# bilancia_smart_full.net
KiCad netlist of a schematic drawn in EAGLE
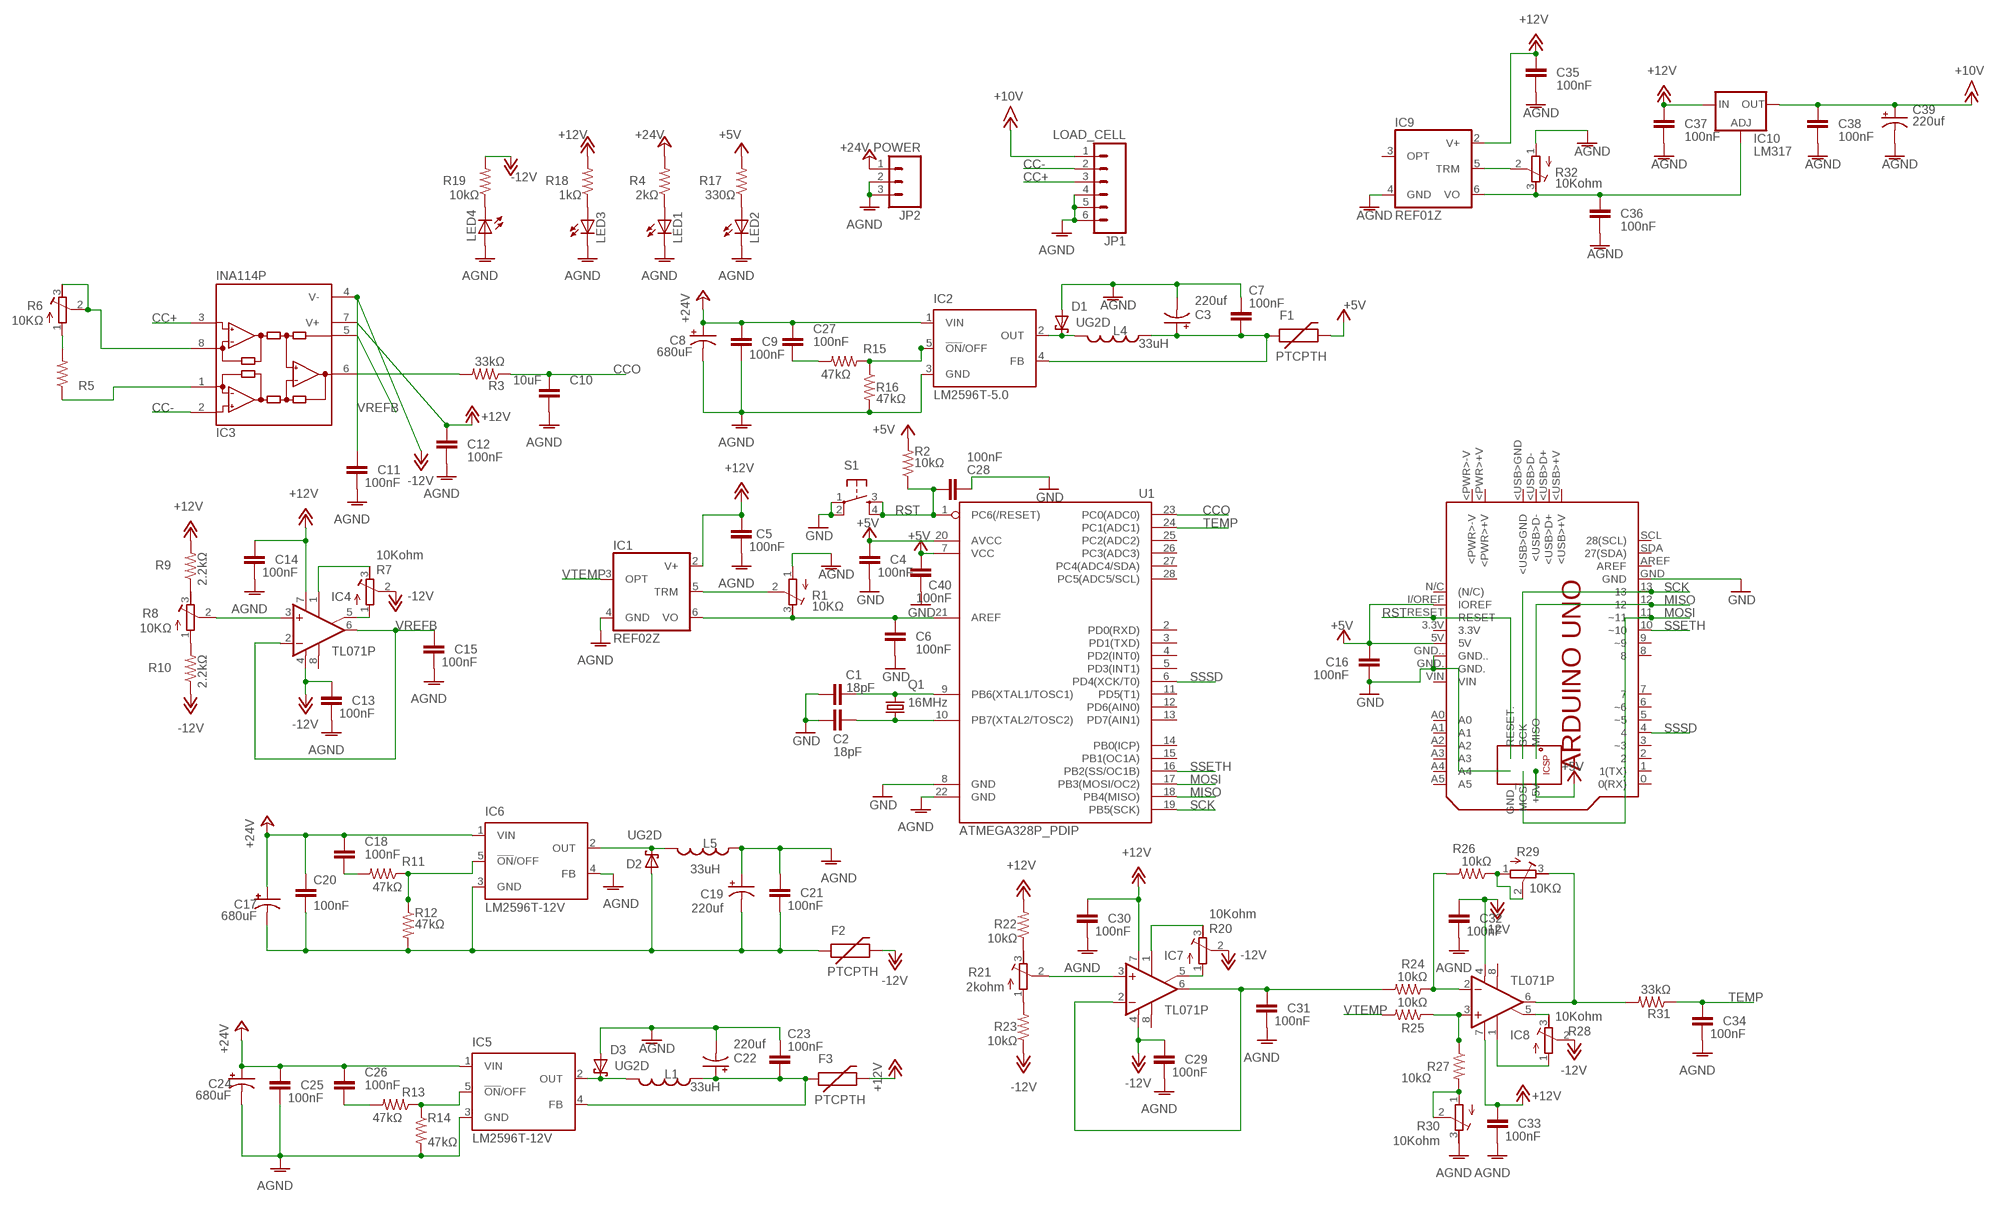
[diagram p0: schematic, sheet 1]

(export (version "E")
  (design (tool "Eeschema 10.0.6"))
  (components
    (comp (ref "C1")
      (value "18pF")
      (footprint "eagle-import:C2.5-2")
      (libsource (lib "eagle-import") (part "C2.5/2"))
    )
    (comp (ref "C2")
      (value "18pF")
      (footprint "eagle-import:C2.5-2")
      (libsource (lib "eagle-import") (part "C2.5/2"))
    )
    (comp (ref "C3")
      (value "220uf")
      (footprint "eagle-import:E5-8,5")
      (libsource (lib "eagle-import") (part "CPOL-USE5-8.5"))
    )
    (comp (ref "C4")
      (value "100nF")
      (footprint "eagle-import:C2.5-2")
      (libsource (lib "eagle-import") (part "C2.5/2"))
    )
    (comp (ref "C5")
      (value "100nF")
      (footprint "eagle-import:C2.5-2")
      (libsource (lib "eagle-import") (part "C2.5/2"))
    )
    (comp (ref "C6")
      (value "100nF")
      (footprint "eagle-import:C2.5-2")
      (libsource (lib "eagle-import") (part "C2.5/2"))
    )
    (comp (ref "C7")
      (value "100nF")
      (footprint "eagle-import:C2.5-2")
      (libsource (lib "eagle-import") (part "C2.5/2"))
    )
    (comp (ref "C8")
      (value "680uF")
      (footprint "eagle-import:E5-8,5")
      (libsource (lib "eagle-import") (part "CPOL-USE5-8.5"))
    )
    (comp (ref "C9")
      (value "100nF")
      (footprint "eagle-import:C2.5-2")
      (libsource (lib "eagle-import") (part "C2.5/2"))
    )
    (comp (ref "C10")
      (value "10uF")
      (footprint "eagle-import:C2.5-2")
      (libsource (lib "eagle-import") (part "C2.5/2"))
    )
    (comp (ref "C11")
      (value "100nF")
      (footprint "eagle-import:C2.5-2")
      (libsource (lib "eagle-import") (part "C2.5/2"))
    )
    (comp (ref "C12")
      (value "100nF")
      (footprint "eagle-import:C2.5-2")
      (libsource (lib "eagle-import") (part "C2.5/2"))
    )
    (comp (ref "C13")
      (value "100nF")
      (footprint "eagle-import:C2.5-2")
      (libsource (lib "eagle-import") (part "C2.5/2"))
    )
    (comp (ref "C14")
      (value "100nF")
      (footprint "eagle-import:C2.5-2")
      (libsource (lib "eagle-import") (part "C2.5/2"))
    )
    (comp (ref "C15")
      (value "100nF")
      (footprint "eagle-import:C2.5-2")
      (libsource (lib "eagle-import") (part "C2.5/2"))
    )
    (comp (ref "C16")
      (value "100nF")
      (footprint "eagle-import:C2.5-2")
      (libsource (lib "eagle-import") (part "C2.5/2"))
    )
    (comp (ref "C17")
      (value "680uF")
      (footprint "eagle-import:E5-8,5")
      (libsource (lib "eagle-import") (part "CPOL-USE5-8.5"))
    )
    (comp (ref "C18")
      (value "100nF")
      (footprint "eagle-import:C2.5-2")
      (libsource (lib "eagle-import") (part "C2.5/2"))
    )
    (comp (ref "C19")
      (value "220uf")
      (footprint "eagle-import:E5-8,5")
      (libsource (lib "eagle-import") (part "CPOL-USE5-8.5"))
    )
    (comp (ref "C20")
      (value "100nF")
      (footprint "eagle-import:C2.5-2")
      (libsource (lib "eagle-import") (part "C2.5/2"))
    )
    (comp (ref "C21")
      (value "100nF")
      (footprint "eagle-import:C2.5-2")
      (libsource (lib "eagle-import") (part "C2.5/2"))
    )
    (comp (ref "C22")
      (value "220uf")
      (footprint "eagle-import:E5-8,5")
      (libsource (lib "eagle-import") (part "CPOL-USE5-8.5"))
    )
    (comp (ref "C23")
      (value "100nF")
      (footprint "eagle-import:C2.5-2")
      (libsource (lib "eagle-import") (part "C2.5/2"))
    )
    (comp (ref "C24")
      (value "680uF")
      (footprint "eagle-import:E5-8,5")
      (libsource (lib "eagle-import") (part "CPOL-USE5-8.5"))
    )
    (comp (ref "C25")
      (value "100nF")
      (footprint "eagle-import:C2.5-2")
      (libsource (lib "eagle-import") (part "C2.5/2"))
    )
    (comp (ref "C26")
      (value "100nF")
      (footprint "eagle-import:C2.5-2")
      (libsource (lib "eagle-import") (part "C2.5/2"))
    )
    (comp (ref "C27")
      (value "100nF")
      (footprint "eagle-import:C2.5-2")
      (libsource (lib "eagle-import") (part "C2.5/2"))
    )
    (comp (ref "C28")
      (value "100nF")
      (footprint "eagle-import:C2.5-2")
      (libsource (lib "eagle-import") (part "C2.5/2"))
    )
    (comp (ref "C29")
      (value "100nF")
      (footprint "eagle-import:C2.5-2")
      (libsource (lib "eagle-import") (part "C2.5/2"))
    )
    (comp (ref "C30")
      (value "100nF")
      (footprint "eagle-import:C2.5-2")
      (libsource (lib "eagle-import") (part "C2.5/2"))
    )
    (comp (ref "C31")
      (value "100nF")
      (footprint "eagle-import:C2.5-2")
      (libsource (lib "eagle-import") (part "C2.5/2"))
    )
    (comp (ref "C32")
      (value "100nF")
      (footprint "eagle-import:C2.5-2")
      (libsource (lib "eagle-import") (part "C2.5/2"))
    )
    (comp (ref "C33")
      (value "100nF")
      (footprint "eagle-import:C2.5-2")
      (libsource (lib "eagle-import") (part "C2.5/2"))
    )
    (comp (ref "C34")
      (value "100nF")
      (footprint "eagle-import:C2.5-2")
      (libsource (lib "eagle-import") (part "C2.5/2"))
    )
    (comp (ref "C35")
      (value "100nF")
      (footprint "eagle-import:C2.5-2")
      (libsource (lib "eagle-import") (part "C2.5/2"))
    )
    (comp (ref "C36")
      (value "100nF")
      (footprint "eagle-import:C2.5-2")
      (libsource (lib "eagle-import") (part "C2.5/2"))
    )
    (comp (ref "C37")
      (value "100nF")
      (footprint "eagle-import:C2.5-2")
      (libsource (lib "eagle-import") (part "C2.5/2"))
    )
    (comp (ref "C38")
      (value "100nF")
      (footprint "eagle-import:C2.5-2")
      (libsource (lib "eagle-import") (part "C2.5/2"))
    )
    (comp (ref "C39")
      (value "220uf")
      (footprint "eagle-import:E5-8,5")
      (libsource (lib "eagle-import") (part "CPOL-USE5-8.5"))
    )
    (comp (ref "C40")
      (value "100nF")
      (footprint "eagle-import:C2.5-2")
      (libsource (lib "eagle-import") (part "C2.5/2"))
    )
    (comp (ref "D1")
      (value "UG2D")
      (footprint "eagle-import:DO41-7")
      (libsource (lib "eagle-import") (part "SCHOTTKY-DIODEDO41-7"))
    )
    (comp (ref "D2")
      (value "UG2D")
      (footprint "eagle-import:DO41-7")
      (libsource (lib "eagle-import") (part "SCHOTTKY-DIODEDO41-7"))
    )
    (comp (ref "D3")
      (value "UG2D")
      (footprint "eagle-import:DO41-7")
      (libsource (lib "eagle-import") (part "SCHOTTKY-DIODEDO41-7"))
    )
    (comp (ref "F1")
      (value "PTCPTH")
      (footprint "eagle-import:PTC")
      (libsource (lib "eagle-import") (part "PTCPTH"))
    )
    (comp (ref "F2")
      (value "PTCPTH")
      (footprint "eagle-import:PTC")
      (libsource (lib "eagle-import") (part "PTCPTH"))
    )
    (comp (ref "F3")
      (value "PTCPTH")
      (footprint "eagle-import:PTC")
      (libsource (lib "eagle-import") (part "PTCPTH"))
    )
    (comp (ref "IC1")
      (value "REF02Z")
      (footprint "eagle-import:DIL08")
      (libsource (lib "eagle-import") (part "REF02Z"))
    )
    (comp (ref "IC2")
      (value "LM2596T-5.0")
      (footprint "eagle-import:T05D")
      (fields (field (name "MPN") "LM2596T-ADJ/LF02"))
      (libsource (lib "eagle-import") (part "LM2596T"))
    )
    (comp (ref "IC3")
      (value "INA114P")
      (footprint "eagle-import:DIL08")
      (fields (field (name "MF") "TEXAS INSTRUMENTS") (field (name "MPN") "INA114BP"))
      (libsource (lib "eagle-import") (part "INA114P"))
    )
    (comp (ref "IC4")
      (value "TL071P")
      (footprint "eagle-import:DIL08")
      (libsource (lib "eagle-import") (part "TL071P"))
    )
    (comp (ref "IC5")
      (value "LM2596T-12V")
      (footprint "eagle-import:T05D")
      (fields (field (name "MPN") "LM2596T-ADJ/LF02"))
      (libsource (lib "eagle-import") (part "LM2596T"))
    )
    (comp (ref "IC6")
      (value "LM2596T-12V")
      (footprint "eagle-import:T05D")
      (fields (field (name "MPN") "LM2596T-ADJ/LF02"))
      (libsource (lib "eagle-import") (part "LM2596T"))
    )
    (comp (ref "IC7")
      (value "TL071P")
      (footprint "eagle-import:DIL08")
      (libsource (lib "eagle-import") (part "TL071P"))
    )
    (comp (ref "IC8")
      (value "TL071P")
      (footprint "eagle-import:DIL08")
      (libsource (lib "eagle-import") (part "TL071P"))
    )
    (comp (ref "IC9")
      (value "REF01Z")
      (footprint "eagle-import:DIL08")
      (libsource (lib "eagle-import") (part "REF01Z"))
    )
    (comp (ref "IC10")
      (value "LM317")
      (footprint "eagle-import:317TL")
      (libsource (lib "eagle-import") (part "LM317TL"))
    )
    (comp (ref "JP1")
      (value "LOAD_CELL")
      (footprint "eagle-import:1X06")
      (libsource (lib "eagle-import") (part "M06SIP"))
    )
    (comp (ref "JP2")
      (value "POWER")
      (footprint "eagle-import:1X03")
      (libsource (lib "eagle-import") (part "M03PTH"))
    )
    (comp (ref "L1")
      (value "33uH")
      (footprint "eagle-import:RLB0912")
      (libsource (lib "eagle-import") (part "INDUCTORRLB0912"))
    )
    (comp (ref "L4")
      (value "33uH")
      (footprint "eagle-import:RLB0912")
      (libsource (lib "eagle-import") (part "INDUCTORRLB0912"))
    )
    (comp (ref "L5")
      (value "33uH")
      (footprint "eagle-import:RLB0912")
      (libsource (lib "eagle-import") (part "INDUCTORRLB0912"))
    )
    (comp (ref "LED1")
      (value "MINIMIDI_LED5MM")
      (footprint "eagle-import:MINIMIDI_LED5MM")
      (libsource (lib "eagle-import") (part "MINIMIDI_LED5MM"))
    )
    (comp (ref "LED2")
      (value "MINIMIDI_LED5MM")
      (footprint "eagle-import:MINIMIDI_LED5MM")
      (libsource (lib "eagle-import") (part "MINIMIDI_LED5MM"))
    )
    (comp (ref "LED3")
      (value "MINIMIDI_LED5MM")
      (footprint "eagle-import:MINIMIDI_LED5MM")
      (libsource (lib "eagle-import") (part "MINIMIDI_LED5MM"))
    )
    (comp (ref "LED4")
      (value "MINIMIDI_LED5MM")
      (footprint "eagle-import:MINIMIDI_LED5MM")
      (libsource (lib "eagle-import") (part "MINIMIDI_LED5MM"))
    )
    (comp (ref "PCB1")
      (value "ARDUINO_UNO")
      (footprint "eagle-import:ARDUINO_UNO")
      (libsource (lib "eagle-import") (part "ARDUINO_UNO"))
    )
    (comp (ref "Q1")
      (value "16MHz")
      (footprint "eagle-import:HC49_S")
      (libsource (lib "eagle-import") (part "CRYSTALHC49S"))
    )
    (comp (ref "R1")
      (value "10KΩ")
      (footprint "eagle-import:RTRIM64W")
      (libsource (lib "eagle-import") (part "R-TRIMM64W"))
    )
    (comp (ref "R2")
      (value "10kΩ")
      (footprint "eagle-import:0207_10")
      (libsource (lib "eagle-import") (part "R-US_0207/10"))
    )
    (comp (ref "R3")
      (value "33kΩ")
      (footprint "eagle-import:0207_10")
      (libsource (lib "eagle-import") (part "R-US_0207/10"))
    )
    (comp (ref "R4")
      (value "2kΩ")
      (footprint "eagle-import:0207_10")
      (libsource (lib "eagle-import") (part "R-US_0207/10"))
    )
    (comp (ref "R5")
      (value "R-US_0207/10")
      (footprint "eagle-import:0207_10")
      (libsource (lib "eagle-import") (part "R-US_0207/10"))
    )
    (comp (ref "R6")
      (value "10KΩ")
      (footprint "eagle-import:RTRIM64W")
      (libsource (lib "eagle-import") (part "R-TRIMM64W"))
    )
    (comp (ref "R7")
      (value "10Kohm")
      (footprint "eagle-import:RTRIM64W")
      (libsource (lib "eagle-import") (part "R-TRIMM64W"))
    )
    (comp (ref "R8")
      (value "10KΩ")
      (footprint "eagle-import:RTRIM64W")
      (libsource (lib "eagle-import") (part "R-TRIMM64W"))
    )
    (comp (ref "R9")
      (value "2.2kΩ")
      (footprint "eagle-import:0207_10")
      (libsource (lib "eagle-import") (part "R-US_0207/10"))
    )
    (comp (ref "R10")
      (value "2.2kΩ")
      (footprint "eagle-import:0207_10")
      (libsource (lib "eagle-import") (part "R-US_0207/10"))
    )
    (comp (ref "R11")
      (value "47kΩ")
      (footprint "eagle-import:0207_10")
      (libsource (lib "eagle-import") (part "R-US_0207/10"))
    )
    (comp (ref "R12")
      (value "47kΩ")
      (footprint "eagle-import:0207_10")
      (libsource (lib "eagle-import") (part "R-US_0207/10"))
    )
    (comp (ref "R13")
      (value "47kΩ")
      (footprint "eagle-import:0207_10")
      (libsource (lib "eagle-import") (part "R-US_0207/10"))
    )
    (comp (ref "R14")
      (value "47kΩ")
      (footprint "eagle-import:0207_10")
      (libsource (lib "eagle-import") (part "R-US_0207/10"))
    )
    (comp (ref "R15")
      (value "47kΩ")
      (footprint "eagle-import:0207_10")
      (libsource (lib "eagle-import") (part "R-US_0207/10"))
    )
    (comp (ref "R16")
      (value "47kΩ")
      (footprint "eagle-import:0207_10")
      (libsource (lib "eagle-import") (part "R-US_0207/10"))
    )
    (comp (ref "R17")
      (value "330Ω")
      (footprint "eagle-import:0207_10")
      (libsource (lib "eagle-import") (part "R-US_0207/10"))
    )
    (comp (ref "R18")
      (value "1kΩ")
      (footprint "eagle-import:0207_10")
      (libsource (lib "eagle-import") (part "R-US_0207/10"))
    )
    (comp (ref "R19")
      (value "10kΩ")
      (footprint "eagle-import:0207_10")
      (libsource (lib "eagle-import") (part "R-US_0207/10"))
    )
    (comp (ref "R20")
      (value "10Kohm")
      (footprint "eagle-import:RTRIM64W")
      (libsource (lib "eagle-import") (part "R-TRIMM64W"))
    )
    (comp (ref "R21")
      (value "2kohm")
      (footprint "eagle-import:RTRIM64W")
      (libsource (lib "eagle-import") (part "R-TRIMM64W"))
    )
    (comp (ref "R22")
      (value "10kΩ")
      (footprint "eagle-import:0207_10")
      (libsource (lib "eagle-import") (part "R-US_0207/10"))
    )
    (comp (ref "R23")
      (value "10kΩ")
      (footprint "eagle-import:0207_10")
      (libsource (lib "eagle-import") (part "R-US_0207/10"))
    )
    (comp (ref "R24")
      (value "10kΩ")
      (footprint "eagle-import:0207_10")
      (libsource (lib "eagle-import") (part "R-US_0207/10"))
    )
    (comp (ref "R25")
      (value "10kΩ")
      (footprint "eagle-import:0207_10")
      (libsource (lib "eagle-import") (part "R-US_0207/10"))
    )
    (comp (ref "R26")
      (value "10kΩ")
      (footprint "eagle-import:0207_10")
      (libsource (lib "eagle-import") (part "R-US_0207/10"))
    )
    (comp (ref "R27")
      (value "10kΩ")
      (footprint "eagle-import:0207_10")
      (libsource (lib "eagle-import") (part "R-US_0207/10"))
    )
    (comp (ref "R28")
      (value "10Kohm")
      (footprint "eagle-import:RTRIM64W")
      (libsource (lib "eagle-import") (part "R-TRIMM64W"))
    )
    (comp (ref "R29")
      (value "10KΩ")
      (footprint "eagle-import:RTRIM64W")
      (libsource (lib "eagle-import") (part "R-TRIMM64W"))
    )
    (comp (ref "R30")
      (value "10Kohm")
      (footprint "eagle-import:RTRIM64W")
      (libsource (lib "eagle-import") (part "R-TRIMM64W"))
    )
    (comp (ref "R31")
      (value "33kΩ")
      (footprint "eagle-import:0207_10")
      (libsource (lib "eagle-import") (part "R-US_0207/10"))
    )
    (comp (ref "R32")
      (value "10Kohm")
      (footprint "eagle-import:RTRIM64W")
      (libsource (lib "eagle-import") (part "R-TRIMM64W"))
    )
    (comp (ref "S1")
      (value "TAC_SWITCHPTH")
      (footprint "eagle-import:TACTILE-PTH")
      (libsource (lib "eagle-import") (part "TAC_SWITCHPTH"))
    )
    (comp (ref "U1")
      (value "ATMEGA328P_PDIP")
      (footprint "eagle-import:DIL28-3")
      (libsource (lib "eagle-import") (part "ATMEGA328P_PDIP"))
    )
  )
  (nets
    (net (code "1") (name "+5V") (class "Default")
      (node (ref "C16") (pin "2") (pinfunction "2_2") (pintype "passive"))
      (node (ref "C4") (pin "2") (pinfunction "2_2") (pintype "passive"))
      (node (ref "C40") (pin "2") (pinfunction "2_2") (pintype "passive"))
      (node (ref "F1") (pin "P$2") (pinfunction "2_P$2") (pintype "bidirectional"))
      (node (ref "PCB1") (pin "+5V") (pinfunction "+5V_+5V") (pintype "bidirectional"))
      (node (ref "PCB1") (pin "5V") (pinfunction "5V_5V") (pintype "bidirectional"))
      (node (ref "PCB1") (pin "I/OREF") (pinfunction "IOREF_I/OREF") (pintype "bidirectional"))
      (node (ref "R17") (pin "2") (pinfunction "2_2") (pintype "passive"))
      (node (ref "R2") (pin "2") (pinfunction "2_2") (pintype "passive"))
      (node (ref "U1") (pin "20") (pinfunction "AVCC_20") (pintype "bidirectional"))
      (node (ref "U1") (pin "7") (pinfunction "VCC_7") (pintype "bidirectional"))
    )
    (net (code "2") (name "+10V") (class "Default")
      (node (ref "C38") (pin "2") (pinfunction "2_2") (pintype "passive"))
      (node (ref "C39") (pin "+") (pinfunction "+_+") (pintype "passive"))
      (node (ref "IC10") (pin "2") (pinfunction "OUT_2") (pintype "passive"))
      (node (ref "JP1") (pin "1") (pinfunction "1_1") (pintype "passive"))
    )
    (net (code "3") (name "+12V") (class "Default")
      (node (ref "C12") (pin "2") (pinfunction "2_2") (pintype "passive"))
      (node (ref "C14") (pin "2") (pinfunction "2_2") (pintype "passive"))
      (node (ref "C30") (pin "2") (pinfunction "2_2") (pintype "passive"))
      (node (ref "C33") (pin "2") (pinfunction "2_2") (pintype "passive"))
      (node (ref "C35") (pin "2") (pinfunction "2_2") (pintype "passive"))
      (node (ref "C37") (pin "2") (pinfunction "2_2") (pintype "passive"))
      (node (ref "C5") (pin "1") (pinfunction "1_1") (pintype "passive"))
      (node (ref "F3") (pin "P$2") (pinfunction "2_P$2") (pintype "bidirectional"))
      (node (ref "IC1") (pin "2") (pinfunction "V+_2") (pintype "power_in"))
      (node (ref "IC10") (pin "3") (pinfunction "IN_3") (pintype "input"))
      (node (ref "IC3") (pin "7") (pinfunction "V+_7") (pintype "power_in"))
      (node (ref "IC4") (pin "7") (pinfunction "V+_7") (pintype "power_in"))
      (node (ref "IC7") (pin "7") (pinfunction "V+_7") (pintype "power_in"))
      (node (ref "IC8") (pin "7") (pinfunction "V+_7") (pintype "power_in"))
      (node (ref "IC9") (pin "2") (pinfunction "V+_2") (pintype "power_in"))
      (node (ref "R18") (pin "2") (pinfunction "2_2") (pintype "passive"))
      (node (ref "R22") (pin "2") (pinfunction "2_2") (pintype "passive"))
      (node (ref "R9") (pin "2") (pinfunction "2_2") (pintype "passive"))
    )
    (net (code "4") (name "+24V") (class "Default")
      (node (ref "C17") (pin "+") (pinfunction "+_+") (pintype "passive"))
      (node (ref "C18") (pin "1") (pinfunction "1_1") (pintype "passive"))
      (node (ref "C20") (pin "1") (pinfunction "1_1") (pintype "passive"))
      (node (ref "C24") (pin "+") (pinfunction "+_+") (pintype "passive"))
      (node (ref "C25") (pin "1") (pinfunction "1_1") (pintype "passive"))
      (node (ref "C26") (pin "1") (pinfunction "1_1") (pintype "passive"))
      (node (ref "C27") (pin "1") (pinfunction "1_1") (pintype "passive"))
      (node (ref "C8") (pin "+") (pinfunction "+_+") (pintype "passive"))
      (node (ref "C9") (pin "1") (pinfunction "1_1") (pintype "passive"))
      (node (ref "IC2") (pin "1") (pinfunction "VIN_1") (pintype "input"))
      (node (ref "IC5") (pin "1") (pinfunction "VIN_1") (pintype "input"))
      (node (ref "IC6") (pin "1") (pinfunction "VIN_1") (pintype "input"))
      (node (ref "JP2") (pin "1") (pinfunction "1_1") (pintype "passive"))
      (node (ref "R4") (pin "2") (pinfunction "2_2") (pintype "passive"))
    )
    (net (code "5") (name "-12V") (class "Default")
      (node (ref "C11") (pin "2") (pinfunction "2_2") (pintype "passive"))
      (node (ref "C13") (pin "2") (pinfunction "2_2") (pintype "passive"))
      (node (ref "C29") (pin "2") (pinfunction "2_2") (pintype "passive"))
      (node (ref "C32") (pin "2") (pinfunction "2_2") (pintype "passive"))
      (node (ref "F2") (pin "P$2") (pinfunction "2_P$2") (pintype "bidirectional"))
      (node (ref "IC3") (pin "4") (pinfunction "V-_4") (pintype "power_in"))
      (node (ref "IC4") (pin "4") (pinfunction "V-_4") (pintype "power_in"))
      (node (ref "IC7") (pin "4") (pinfunction "V-_4") (pintype "power_in"))
      (node (ref "IC8") (pin "4") (pinfunction "V-_4") (pintype "power_in"))
      (node (ref "R10") (pin "1") (pinfunction "1_1") (pintype "passive"))
      (node (ref "R19") (pin "2") (pinfunction "2_2") (pintype "passive"))
      (node (ref "R20") (pin "2") (pinfunction "S_2") (pintype "passive"))
      (node (ref "R23") (pin "1") (pinfunction "1_1") (pintype "passive"))
      (node (ref "R28") (pin "2") (pinfunction "S_2") (pintype "passive"))
      (node (ref "R7") (pin "2") (pinfunction "S_2") (pintype "passive"))
    )
    (net (code "6") (name "/CC+") (class "Default")
      (node (ref "IC3") (pin "3") (pinfunction "+IN_3") (pintype "input"))
      (node (ref "JP1") (pin "3") (pinfunction "3_3") (pintype "passive"))
    )
    (net (code "7") (name "/CC-") (class "Default")
      (node (ref "IC3") (pin "2") (pinfunction "-IN_2") (pintype "input"))
      (node (ref "JP1") (pin "2") (pinfunction "2_2") (pintype "passive"))
    )
    (net (code "8") (name "/CCO") (class "Default")
      (node (ref "C10") (pin "2") (pinfunction "2_2") (pintype "passive"))
      (node (ref "R3") (pin "1") (pinfunction "1_1") (pintype "passive"))
      (node (ref "U1") (pin "23") (pinfunction "PC0(ADC0)_23") (pintype "bidirectional"))
    )
    (net (code "9") (name "/MISO") (class "Default")
      (node (ref "PCB1") (pin "12") (pinfunction "12_12") (pintype "bidirectional"))
      (node (ref "PCB1") (pin "MISO") (pinfunction "MISO_MISO") (pintype "bidirectional"))
      (node (ref "U1") (pin "18") (pinfunction "PB4(MISO)_18") (pintype "bidirectional"))
    )
    (net (code "10") (name "/MOSI") (class "Default")
      (node (ref "PCB1") (pin "11") (pinfunction "~{11}_11") (pintype "bidirectional"))
      (node (ref "PCB1") (pin "MOSI") (pinfunction "MOSI_MOSI") (pintype "bidirectional"))
      (node (ref "U1") (pin "17") (pinfunction "PB3(MOSI/OC2)_17") (pintype "bidirectional"))
    )
    (net (code "11") (name "/RST") (class "Default")
      (node (ref "C28") (pin "2") (pinfunction "2_2") (pintype "passive"))
      (node (ref "PCB1") (pin "RESET") (pinfunction "RESET_RESET") (pintype "bidirectional"))
      (node (ref "PCB1") (pin "RESET.") (pinfunction "RESET._RESET.") (pintype "bidirectional"))
      (node (ref "R2") (pin "1") (pinfunction "1_1") (pintype "passive"))
      (node (ref "S1") (pin "3") (pinfunction "3_3") (pintype "passive"))
      (node (ref "S1") (pin "4") (pinfunction "4_4") (pintype "passive"))
      (node (ref "U1") (pin "1") (pinfunction "PC6(/RESET)_1") (pintype "bidirectional"))
    )
    (net (code "12") (name "/SCK") (class "Default")
      (node (ref "PCB1") (pin "13") (pinfunction "13_13") (pintype "bidirectional"))
      (node (ref "PCB1") (pin "SCK") (pinfunction "SCK_SCK") (pintype "bidirectional"))
      (node (ref "U1") (pin "19") (pinfunction "PB5(SCK)_19") (pintype "bidirectional"))
    )
    (net (code "13") (name "/SSETH") (class "Default")
      (node (ref "PCB1") (pin "10") (pinfunction "~{10}_10") (pintype "bidirectional"))
      (node (ref "U1") (pin "16") (pinfunction "PB2(SS/OC1B)_16") (pintype "bidirectional"))
    )
    (net (code "14") (name "/SSSD") (class "Default")
      (node (ref "PCB1") (pin "4") (pinfunction "4_4") (pintype "bidirectional"))
      (node (ref "U1") (pin "6") (pinfunction "PD4(XCK/T0)_6") (pintype "bidirectional"))
    )
    (net (code "15") (name "/TEMP") (class "Default")
      (node (ref "C34") (pin "2") (pinfunction "2_2") (pintype "passive"))
      (node (ref "R31") (pin "1") (pinfunction "1_1") (pintype "passive"))
      (node (ref "U1") (pin "24") (pinfunction "PC1(ADC1)_24") (pintype "bidirectional"))
    )
    (net (code "16") (name "/VREFB") (class "Default")
      (node (ref "C15") (pin "2") (pinfunction "2_2") (pintype "passive"))
      (node (ref "IC3") (pin "5") (pinfunction "REF_5") (pintype "passive"))
      (node (ref "IC4") (pin "2") (pinfunction "-IN_2") (pintype "input"))
      (node (ref "IC4") (pin "6") (pinfunction "OUT_6") (pintype "output"))
    )
    (net (code "17") (name "/VTEMP") (class "Default")
      (node (ref "IC1") (pin "3") (pinfunction "OPT_3") (pintype "output"))
      (node (ref "R25") (pin "2") (pinfunction "2_2") (pintype "passive"))
    )
    (net (code "18") (name "AGND") (class "Default")
      (node (ref "C10") (pin "1") (pinfunction "1_1") (pintype "passive"))
      (node (ref "C11") (pin "1") (pinfunction "1_1") (pintype "passive"))
      (node (ref "C12") (pin "1") (pinfunction "1_1") (pintype "passive"))
      (node (ref "C13") (pin "1") (pinfunction "1_1") (pintype "passive"))
      (node (ref "C14") (pin "1") (pinfunction "1_1") (pintype "passive"))
      (node (ref "C15") (pin "1") (pinfunction "1_1") (pintype "passive"))
      (node (ref "C19") (pin "+") (pinfunction "+_+") (pintype "passive"))
      (node (ref "C21") (pin "1") (pinfunction "1_1") (pintype "passive"))
      (node (ref "C22") (pin "-") (pinfunction "-_-") (pintype "passive"))
      (node (ref "C23") (pin "2") (pinfunction "2_2") (pintype "passive"))
      (node (ref "C24") (pin "-") (pinfunction "-_-") (pintype "passive"))
      (node (ref "C25") (pin "2") (pinfunction "2_2") (pintype "passive"))
      (node (ref "C29") (pin "1") (pinfunction "1_1") (pintype "passive"))
      (node (ref "C3") (pin "-") (pinfunction "-_-") (pintype "passive"))
      (node (ref "C30") (pin "1") (pinfunction "1_1") (pintype "passive"))
      (node (ref "C31") (pin "1") (pinfunction "1_1") (pintype "passive"))
      (node (ref "C32") (pin "1") (pinfunction "1_1") (pintype "passive"))
      (node (ref "C33") (pin "1") (pinfunction "1_1") (pintype "passive"))
      (node (ref "C34") (pin "1") (pinfunction "1_1") (pintype "passive"))
      (node (ref "C35") (pin "1") (pinfunction "1_1") (pintype "passive"))
      (node (ref "C36") (pin "1") (pinfunction "1_1") (pintype "passive"))
      (node (ref "C37") (pin "1") (pinfunction "1_1") (pintype "passive"))
      (node (ref "C38") (pin "1") (pinfunction "1_1") (pintype "passive"))
      (node (ref "C39") (pin "-") (pinfunction "-_-") (pintype "passive"))
      (node (ref "C5") (pin "2") (pinfunction "2_2") (pintype "passive"))
      (node (ref "C7") (pin "2") (pinfunction "2_2") (pintype "passive"))
      (node (ref "C8") (pin "-") (pinfunction "-_-") (pintype "passive"))
      (node (ref "C9") (pin "2") (pinfunction "2_2") (pintype "passive"))
      (node (ref "D1") (pin "A") (pinfunction "A_A") (pintype "passive"))
      (node (ref "D3") (pin "A") (pinfunction "A_A") (pintype "passive"))
      (node (ref "IC1") (pin "4") (pinfunction "GND_4") (pintype "power_in"))
      (node (ref "IC2") (pin "3") (pinfunction "GND_3") (pintype "power_in"))
      (node (ref "IC5") (pin "3") (pinfunction "GND_3") (pintype "power_in"))
      (node (ref "IC6") (pin "4") (pinfunction "FB_4") (pintype "input"))
      (node (ref "IC9") (pin "4") (pinfunction "GND_4") (pintype "power_in"))
      (node (ref "JP1") (pin "4") (pinfunction "4_4") (pintype "passive"))
      (node (ref "JP1") (pin "5") (pinfunction "5_5") (pintype "passive"))
      (node (ref "JP1") (pin "6") (pinfunction "6_6") (pintype "passive"))
      (node (ref "JP2") (pin "2") (pinfunction "2_2") (pintype "passive"))
      (node (ref "JP2") (pin "3") (pinfunction "3_3") (pintype "passive"))
      (node (ref "L5") (pin "1") (pinfunction "1_1") (pintype "passive"))
      (node (ref "LED1") (pin "K") (pinfunction "C_K") (pintype "passive"))
      (node (ref "LED2") (pin "K") (pinfunction "C_K") (pintype "passive"))
      (node (ref "LED3") (pin "K") (pinfunction "C_K") (pintype "passive"))
      (node (ref "LED4") (pin "A") (pinfunction "A_A") (pintype "passive"))
      (node (ref "R1") (pin "1") (pinfunction "E_1") (pintype "passive"))
      (node (ref "R14") (pin "2") (pinfunction "2_2") (pintype "passive"))
      (node (ref "R16") (pin "2") (pinfunction "2_2") (pintype "passive"))
      (node (ref "R30") (pin "3") (pinfunction "A_3") (pintype "passive"))
      (node (ref "R32") (pin "1") (pinfunction "E_1") (pintype "passive"))
      (node (ref "U1") (pin "22") (pinfunction "GND_22") (pintype "bidirectional"))
    )
    (net (code "19") (name "GND") (class "Default")
      (node (ref "C1") (pin "1") (pinfunction "1_1") (pintype "passive"))
      (node (ref "C16") (pin "1") (pinfunction "1_1") (pintype "passive"))
      (node (ref "C2") (pin "1") (pinfunction "1_1") (pintype "passive"))
      (node (ref "C28") (pin "1") (pinfunction "1_1") (pintype "passive"))
      (node (ref "C4") (pin "1") (pinfunction "1_1") (pintype "passive"))
      (node (ref "C40") (pin "1") (pinfunction "1_1") (pintype "passive"))
      (node (ref "C6") (pin "1") (pinfunction "1_1") (pintype "passive"))
      (node (ref "PCB1") (pin "GND") (pinfunction "GND_GND") (pintype "bidirectional"))
      (node (ref "PCB1") (pin "GND.") (pinfunction "GND._GND.") (pintype "bidirectional"))
      (node (ref "PCB1") (pin "GND..") (pinfunction "GND.._GND..") (pintype "bidirectional"))
      (node (ref "PCB1") (pin "GND_") (pinfunction "GND__GND_") (pintype "bidirectional"))
      (node (ref "S1") (pin "1") (pinfunction "1_1") (pintype "passive"))
      (node (ref "S1") (pin "2") (pinfunction "2_2") (pintype "passive"))
      (node (ref "U1") (pin "8") (pinfunction "GND_8") (pintype "bidirectional"))
    )
    (net (code "20") (name "Net-(C18-Pad2)") (class "Default")
      (node (ref "C18") (pin "2") (pinfunction "2_2") (pintype "passive"))
      (node (ref "R11") (pin "2") (pinfunction "2_2") (pintype "passive"))
    )
    (net (code "21") (name "Net-(C26-Pad2)") (class "Default")
      (node (ref "C26") (pin "2") (pinfunction "2_2") (pintype "passive"))
      (node (ref "R13") (pin "2") (pinfunction "2_2") (pintype "passive"))
    )
    (net (code "22") (name "Net-(C27-Pad2)") (class "Default")
      (node (ref "C27") (pin "2") (pinfunction "2_2") (pintype "passive"))
      (node (ref "R15") (pin "2") (pinfunction "2_2") (pintype "passive"))
    )
    (net (code "23") (name "Net-(F1-1)") (class "Default")
      (node (ref "C3") (pin "+") (pinfunction "+_+") (pintype "passive"))
      (node (ref "C7") (pin "1") (pinfunction "1_1") (pintype "passive"))
      (node (ref "F1") (pin "P$1") (pinfunction "1_P$1") (pintype "bidirectional"))
      (node (ref "IC2") (pin "4") (pinfunction "FB_4") (pintype "input"))
      (node (ref "L4") (pin "1") (pinfunction "1_1") (pintype "passive"))
    )
    (net (code "24") (name "Net-(F2-1)") (class "Default")
      (node (ref "C17") (pin "-") (pinfunction "-_-") (pintype "passive"))
      (node (ref "C19") (pin "-") (pinfunction "-_-") (pintype "passive"))
      (node (ref "C20") (pin "2") (pinfunction "2_2") (pintype "passive"))
      (node (ref "C21") (pin "2") (pinfunction "2_2") (pintype "passive"))
      (node (ref "D2") (pin "A") (pinfunction "A_A") (pintype "passive"))
      (node (ref "F2") (pin "P$1") (pinfunction "1_P$1") (pintype "bidirectional"))
      (node (ref "IC6") (pin "3") (pinfunction "GND_3") (pintype "power_in"))
      (node (ref "R12") (pin "2") (pinfunction "2_2") (pintype "passive"))
    )
    (net (code "25") (name "Net-(F3-1)") (class "Default")
      (node (ref "C22") (pin "+") (pinfunction "+_+") (pintype "passive"))
      (node (ref "C23") (pin "1") (pinfunction "1_1") (pintype "passive"))
      (node (ref "F3") (pin "P$1") (pinfunction "1_P$1") (pintype "bidirectional"))
      (node (ref "IC5") (pin "4") (pinfunction "FB_4") (pintype "input"))
      (node (ref "L1") (pin "1") (pinfunction "1_1") (pintype "passive"))
    )
    (net (code "26") (name "Net-(IC1-TRM)") (class "Default")
      (node (ref "IC1") (pin "5") (pinfunction "TRM_5") (pintype "input"))
      (node (ref "R1") (pin "2") (pinfunction "S_2") (pintype "passive"))
    )
    (net (code "27") (name "Net-(IC1-VO)") (class "Default")
      (node (ref "C6") (pin "2") (pinfunction "2_2") (pintype "passive"))
      (node (ref "IC1") (pin "6") (pinfunction "VO_6") (pintype "output"))
      (node (ref "R1") (pin "3") (pinfunction "A_3") (pintype "passive"))
      (node (ref "U1") (pin "21") (pinfunction "AREF_21") (pintype "bidirectional"))
    )
    (net (code "28") (name "Net-(IC2-OUT)") (class "Default")
      (node (ref "D1") (pin "C") (pinfunction "C_C") (pintype "passive"))
      (node (ref "IC2") (pin "2") (pinfunction "OUT_2") (pintype "output"))
      (node (ref "L4") (pin "2") (pinfunction "2_2") (pintype "passive"))
    )
    (net (code "29") (name "Net-(IC2-~{ON}{slash}OFF)") (class "Default")
      (node (ref "IC2") (pin "5") (pinfunction "~{ON}/OFF_5") (pintype "input"))
      (node (ref "R15") (pin "1") (pinfunction "1_1") (pintype "passive"))
      (node (ref "R16") (pin "1") (pinfunction "1_1") (pintype "passive"))
    )
    (net (code "30") (name "Net-(IC3-OUT)") (class "Default")
      (node (ref "IC3") (pin "6") (pinfunction "OUT_6") (pintype "output"))
      (node (ref "R3") (pin "2") (pinfunction "2_2") (pintype "passive"))
    )
    (net (code "31") (name "Net-(IC3-RG-Pad1)") (class "Default")
      (node (ref "IC3") (pin "1") (pinfunction "RG_1") (pintype "passive"))
      (node (ref "R5") (pin "1") (pinfunction "1_1") (pintype "passive"))
    )
    (net (code "32") (name "Net-(IC4-+IN)") (class "Default")
      (node (ref "IC4") (pin "3") (pinfunction "+IN_3") (pintype "input"))
      (node (ref "R8") (pin "2") (pinfunction "S_2") (pintype "passive"))
    )
    (net (code "33") (name "Net-(IC4-ON1)") (class "Default")
      (node (ref "IC4") (pin "1") (pinfunction "ON1_1") (pintype "passive"))
      (node (ref "R7") (pin "3") (pinfunction "A_3") (pintype "passive"))
    )
    (net (code "34") (name "Net-(IC4-ON2)") (class "Default")
      (node (ref "IC4") (pin "5") (pinfunction "ON2_5") (pintype "passive"))
      (node (ref "R7") (pin "1") (pinfunction "E_1") (pintype "passive"))
    )
    (net (code "35") (name "Net-(IC5-OUT)") (class "Default")
      (node (ref "D3") (pin "C") (pinfunction "C_C") (pintype "passive"))
      (node (ref "IC5") (pin "2") (pinfunction "OUT_2") (pintype "output"))
      (node (ref "L1") (pin "2") (pinfunction "2_2") (pintype "passive"))
    )
    (net (code "36") (name "Net-(IC5-~{ON}{slash}OFF)") (class "Default")
      (node (ref "IC5") (pin "5") (pinfunction "~{ON}/OFF_5") (pintype "input"))
      (node (ref "R13") (pin "1") (pinfunction "1_1") (pintype "passive"))
      (node (ref "R14") (pin "1") (pinfunction "1_1") (pintype "passive"))
    )
    (net (code "37") (name "Net-(IC6-OUT)") (class "Default")
      (node (ref "D2") (pin "C") (pinfunction "C_C") (pintype "passive"))
      (node (ref "IC6") (pin "2") (pinfunction "OUT_2") (pintype "output"))
      (node (ref "L5") (pin "2") (pinfunction "2_2") (pintype "passive"))
    )
    (net (code "38") (name "Net-(IC6-~{ON}{slash}OFF)") (class "Default")
      (node (ref "IC6") (pin "5") (pinfunction "~{ON}/OFF_5") (pintype "input"))
      (node (ref "R11") (pin "1") (pinfunction "1_1") (pintype "passive"))
      (node (ref "R12") (pin "1") (pinfunction "1_1") (pintype "passive"))
    )
    (net (code "39") (name "Net-(IC7-+IN)") (class "Default")
      (node (ref "IC7") (pin "3") (pinfunction "+IN_3") (pintype "input"))
      (node (ref "R21") (pin "2") (pinfunction "S_2") (pintype "passive"))
    )
    (net (code "40") (name "Net-(IC7--IN)") (class "Default")
      (node (ref "C31") (pin "2") (pinfunction "2_2") (pintype "passive"))
      (node (ref "IC7") (pin "2") (pinfunction "-IN_2") (pintype "input"))
      (node (ref "IC7") (pin "6") (pinfunction "OUT_6") (pintype "output"))
      (node (ref "R24") (pin "2") (pinfunction "2_2") (pintype "passive"))
    )
    (net (code "41") (name "Net-(IC7-ON1)") (class "Default")
      (node (ref "IC7") (pin "1") (pinfunction "ON1_1") (pintype "passive"))
      (node (ref "R20") (pin "3") (pinfunction "A_3") (pintype "passive"))
    )
    (net (code "42") (name "Net-(IC7-ON2)") (class "Default")
      (node (ref "IC7") (pin "5") (pinfunction "ON2_5") (pintype "passive"))
      (node (ref "R20") (pin "1") (pinfunction "E_1") (pintype "passive"))
    )
    (net (code "43") (name "Net-(IC8-+IN)") (class "Default")
      (node (ref "IC8") (pin "3") (pinfunction "+IN_3") (pintype "input"))
      (node (ref "R25") (pin "1") (pinfunction "1_1") (pintype "passive"))
      (node (ref "R27") (pin "1") (pinfunction "1_1") (pintype "passive"))
    )
    (net (code "44") (name "Net-(IC8--IN)") (class "Default")
      (node (ref "IC8") (pin "2") (pinfunction "-IN_2") (pintype "input"))
      (node (ref "R24") (pin "1") (pinfunction "1_1") (pintype "passive"))
      (node (ref "R26") (pin "2") (pinfunction "2_2") (pintype "passive"))
    )
    (net (code "45") (name "Net-(IC8-ON1)") (class "Default")
      (node (ref "IC8") (pin "1") (pinfunction "ON1_1") (pintype "passive"))
      (node (ref "R28") (pin "1") (pinfunction "E_1") (pintype "passive"))
    )
    (net (code "46") (name "Net-(IC8-ON2)") (class "Default")
      (node (ref "IC8") (pin "5") (pinfunction "ON2_5") (pintype "passive"))
      (node (ref "R28") (pin "3") (pinfunction "A_3") (pintype "passive"))
    )
    (net (code "47") (name "Net-(IC8-OUT)") (class "Default")
      (node (ref "IC8") (pin "6") (pinfunction "OUT_6") (pintype "output"))
      (node (ref "R29") (pin "3") (pinfunction "A_3") (pintype "passive"))
      (node (ref "R31") (pin "2") (pinfunction "2_2") (pintype "passive"))
    )
    (net (code "48") (name "Net-(IC9-TRM)") (class "Default")
      (node (ref "IC9") (pin "5") (pinfunction "TRM_5") (pintype "input"))
      (node (ref "R32") (pin "2") (pinfunction "S_2") (pintype "passive"))
    )
    (net (code "49") (name "Net-(IC10-ADJ)") (class "Default")
      (node (ref "C36") (pin "2") (pinfunction "2_2") (pintype "passive"))
      (node (ref "IC10") (pin "1") (pinfunction "ADJ_1") (pintype "input"))
      (node (ref "IC9") (pin "6") (pinfunction "VO_6") (pintype "output"))
      (node (ref "R32") (pin "3") (pinfunction "A_3") (pintype "passive"))
    )
    (net (code "50") (name "Net-(LED1-PadA)") (class "Default")
      (node (ref "LED1") (pin "A") (pinfunction "A_A") (pintype "passive"))
      (node (ref "R4") (pin "1") (pinfunction "1_1") (pintype "passive"))
    )
    (net (code "51") (name "Net-(LED2-PadA)") (class "Default")
      (node (ref "LED2") (pin "A") (pinfunction "A_A") (pintype "passive"))
      (node (ref "R17") (pin "1") (pinfunction "1_1") (pintype "passive"))
    )
    (net (code "52") (name "Net-(LED3-PadA)") (class "Default")
      (node (ref "LED3") (pin "A") (pinfunction "A_A") (pintype "passive"))
      (node (ref "R18") (pin "1") (pinfunction "1_1") (pintype "passive"))
    )
    (net (code "53") (name "Net-(LED4-C)") (class "Default")
      (node (ref "LED4") (pin "K") (pinfunction "C_K") (pintype "passive"))
      (node (ref "R19") (pin "1") (pinfunction "1_1") (pintype "passive"))
    )
    (net (code "54") (name "Net-(R6-A)") (class "Default")
      (node (ref "IC3") (pin "8") (pinfunction "RG_8") (pintype "passive"))
      (node (ref "R6") (pin "2") (pinfunction "S_2") (pintype "passive"))
      (node (ref "R6") (pin "3") (pinfunction "A_3") (pintype "passive"))
    )
    (net (code "55") (name "Net-(R6-E)") (class "Default")
      (node (ref "R5") (pin "2") (pinfunction "2_2") (pintype "passive"))
      (node (ref "R6") (pin "1") (pinfunction "E_1") (pintype "passive"))
    )
    (net (code "56") (name "Net-(R8-A)") (class "Default")
      (node (ref "R8") (pin "3") (pinfunction "A_3") (pintype "passive"))
      (node (ref "R9") (pin "1") (pinfunction "1_1") (pintype "passive"))
    )
    (net (code "57") (name "Net-(R8-E)") (class "Default")
      (node (ref "R10") (pin "2") (pinfunction "2_2") (pintype "passive"))
      (node (ref "R8") (pin "1") (pinfunction "E_1") (pintype "passive"))
    )
    (net (code "58") (name "Net-(R21-A)") (class "Default")
      (node (ref "R21") (pin "3") (pinfunction "A_3") (pintype "passive"))
      (node (ref "R22") (pin "1") (pinfunction "1_1") (pintype "passive"))
    )
    (net (code "59") (name "Net-(R21-E)") (class "Default")
      (node (ref "R21") (pin "1") (pinfunction "E_1") (pintype "passive"))
      (node (ref "R23") (pin "2") (pinfunction "2_2") (pintype "passive"))
    )
    (net (code "60") (name "Net-(R29-E)") (class "Default")
      (node (ref "R26") (pin "1") (pinfunction "1_1") (pintype "passive"))
      (node (ref "R29") (pin "1") (pinfunction "E_1") (pintype "passive"))
      (node (ref "R29") (pin "2") (pinfunction "S_2") (pintype "passive"))
    )
    (net (code "61") (name "Net-(R30-E)") (class "Default")
      (node (ref "R27") (pin "2") (pinfunction "2_2") (pintype "passive"))
      (node (ref "R30") (pin "1") (pinfunction "E_1") (pintype "passive"))
      (node (ref "R30") (pin "2") (pinfunction "S_2") (pintype "passive"))
    )
    (net (code "62") (name "Net-(U1-PB6(XTAL1{slash}TOSC1))") (class "Default")
      (node (ref "C1") (pin "2") (pinfunction "2_2") (pintype "passive"))
      (node (ref "Q1") (pin "1") (pinfunction "1_1") (pintype "passive"))
      (node (ref "U1") (pin "9") (pinfunction "PB6(XTAL1/TOSC1)_9") (pintype "bidirectional"))
    )
    (net (code "63") (name "Net-(U1-PB7(XTAL2{slash}TOSC2))") (class "Default")
      (node (ref "C2") (pin "2") (pinfunction "2_2") (pintype "passive"))
      (node (ref "Q1") (pin "2") (pinfunction "2_2") (pintype "passive"))
      (node (ref "U1") (pin "10") (pinfunction "PB7(XTAL2/TOSC2)_10") (pintype "bidirectional"))
    )
    (net (code "64") (name "unconnected-(IC4-OPT-Pad8)") (class "Default")
      (node (ref "IC4") (pin "8") (pinfunction "OPT_8") (pintype "passive"))
    )
    (net (code "65") (name "unconnected-(IC7-OPT-Pad8)") (class "Default")
      (node (ref "IC7") (pin "8") (pinfunction "OPT_8") (pintype "passive"))
    )
    (net (code "66") (name "unconnected-(IC8-OPT-Pad8)") (class "Default")
      (node (ref "IC8") (pin "8") (pinfunction "OPT_8") (pintype "passive"))
    )
    (net (code "67") (name "unconnected-(IC9-OPT-Pad3)") (class "Default")
      (node (ref "IC9") (pin "3") (pinfunction "OPT_3") (pintype "output"))
    )
    (net (code "68") (name "unconnected-(PCB1-(N{slash}C)-PadN{slash}C)") (class "Default")
      (node (ref "PCB1") (pin "N/C") (pinfunction "(N/C)_N/C") (pintype "bidirectional"))
    )
    (net (code "69") (name "unconnected-(PCB1-0(RX)-Pad0)") (class "Default")
      (node (ref "PCB1") (pin "0") (pinfunction "0(RX)_0") (pintype "bidirectional"))
    )
    (net (code "70") (name "unconnected-(PCB1-1(TX)-Pad1)") (class "Default")
      (node (ref "PCB1") (pin "1") (pinfunction "1(TX)_1") (pintype "bidirectional"))
    )
    (net (code "71") (name "unconnected-(PCB1-27(SDA)-PadSDA)") (class "Default")
      (node (ref "PCB1") (pin "SDA") (pinfunction "27(SDA)_SDA") (pintype "bidirectional"))
    )
    (net (code "72") (name "unconnected-(PCB1-28(SCL)-PadSCL)") (class "Default")
      (node (ref "PCB1") (pin "SCL") (pinfunction "28(SCL)_SCL") (pintype "bidirectional"))
    )
    (net (code "73") (name "unconnected-(PCB1-Pad2)") (class "Default")
      (node (ref "PCB1") (pin "2") (pinfunction "2_2") (pintype "bidirectional"))
    )
    (net (code "74") (name "unconnected-(PCB1-Pad3.3V)") (class "Default")
      (node (ref "PCB1") (pin "3.3V") (pinfunction "3.3V_3.3V") (pintype "bidirectional"))
    )
    (net (code "75") (name "unconnected-(PCB1-Pad7)") (class "Default")
      (node (ref "PCB1") (pin "7") (pinfunction "7_7") (pintype "bidirectional"))
    )
    (net (code "76") (name "unconnected-(PCB1-Pad8)") (class "Default")
      (node (ref "PCB1") (pin "8") (pinfunction "8_8") (pintype "bidirectional"))
    )
    (net (code "77") (name "unconnected-(PCB1-Pad<PWR>+V)") (class "Default")
      (node (ref "PCB1") (pin "<PWR>+V") (pinfunction "<PWR>+V_<PWR>+V") (pintype "bidirectional"))
    )
    (net (code "78") (name "unconnected-(PCB1-Pad<PWR>-V)") (class "Default")
      (node (ref "PCB1") (pin "<PWR>-V") (pinfunction "<PWR>-V_<PWR>-V") (pintype "bidirectional"))
    )
    (net (code "79") (name "unconnected-(PCB1-Pad<USB>+V)") (class "Default")
      (node (ref "PCB1") (pin "<USB>+V") (pinfunction "<USB>+V_<USB>+V") (pintype "bidirectional"))
    )
    (net (code "80") (name "unconnected-(PCB1-Pad<USB>D+)") (class "Default")
      (node (ref "PCB1") (pin "<USB>D+") (pinfunction "<USB>D+_<USB>D+") (pintype "bidirectional"))
    )
    (net (code "81") (name "unconnected-(PCB1-Pad<USB>D-)") (class "Default")
      (node (ref "PCB1") (pin "<USB>D-") (pinfunction "<USB>D-_<USB>D-") (pintype "bidirectional"))
    )
    (net (code "82") (name "unconnected-(PCB1-Pad<USB>GND)") (class "Default")
      (node (ref "PCB1") (pin "<USB>GND") (pinfunction "<USB>GND_<USB>GND") (pintype "bidirectional"))
    )
    (net (code "83") (name "unconnected-(PCB1-PadA0)") (class "Default")
      (node (ref "PCB1") (pin "A0") (pinfunction "A0_A0") (pintype "bidirectional"))
    )
    (net (code "84") (name "unconnected-(PCB1-PadA1)") (class "Default")
      (node (ref "PCB1") (pin "A1") (pinfunction "A1_A1") (pintype "bidirectional"))
    )
    (net (code "85") (name "unconnected-(PCB1-PadA2)") (class "Default")
      (node (ref "PCB1") (pin "A2") (pinfunction "A2_A2") (pintype "bidirectional"))
    )
    (net (code "86") (name "unconnected-(PCB1-PadA3)") (class "Default")
      (node (ref "PCB1") (pin "A3") (pinfunction "A3_A3") (pintype "bidirectional"))
    )
    (net (code "87") (name "unconnected-(PCB1-PadA4)") (class "Default")
      (node (ref "PCB1") (pin "A4") (pinfunction "A4_A4") (pintype "bidirectional"))
    )
    (net (code "88") (name "unconnected-(PCB1-PadA5)") (class "Default")
      (node (ref "PCB1") (pin "A5") (pinfunction "A5_A5") (pintype "bidirectional"))
    )
    (net (code "89") (name "unconnected-(PCB1-PadAREF)") (class "Default")
      (node (ref "PCB1") (pin "AREF") (pinfunction "AREF_AREF") (pintype "bidirectional"))
    )
    (net (code "90") (name "unconnected-(PCB1-PadVIN)") (class "Default")
      (node (ref "PCB1") (pin "VIN") (pinfunction "VIN_VIN") (pintype "bidirectional"))
    )
    (net (code "91") (name "unconnected-(PCB1-~{3}-Pad3)") (class "Default")
      (node (ref "PCB1") (pin "3") (pinfunction "~{3}_3") (pintype "bidirectional"))
    )
    (net (code "92") (name "unconnected-(PCB1-~{5}-Pad5)") (class "Default")
      (node (ref "PCB1") (pin "5") (pinfunction "~{5}_5") (pintype "bidirectional"))
    )
    (net (code "93") (name "unconnected-(PCB1-~{6}-Pad6)") (class "Default")
      (node (ref "PCB1") (pin "6") (pinfunction "~{6}_6") (pintype "bidirectional"))
    )
    (net (code "94") (name "unconnected-(PCB1-~{9}-Pad9)") (class "Default")
      (node (ref "PCB1") (pin "9") (pinfunction "~{9}_9") (pintype "bidirectional"))
    )
    (net (code "95") (name "unconnected-(U1-PB0(ICP)-Pad14)") (class "Default")
      (node (ref "U1") (pin "14") (pinfunction "PB0(ICP)_14") (pintype "bidirectional"))
    )
    (net (code "96") (name "unconnected-(U1-PB1(OC1A)-Pad15)") (class "Default")
      (node (ref "U1") (pin "15") (pinfunction "PB1(OC1A)_15") (pintype "bidirectional"))
    )
    (net (code "97") (name "unconnected-(U1-PC2(ADC2)-Pad25)") (class "Default")
      (node (ref "U1") (pin "25") (pinfunction "PC2(ADC2)_25") (pintype "bidirectional"))
    )
    (net (code "98") (name "unconnected-(U1-PC3(ADC3)-Pad26)") (class "Default")
      (node (ref "U1") (pin "26") (pinfunction "PC3(ADC3)_26") (pintype "bidirectional"))
    )
    (net (code "99") (name "unconnected-(U1-PC4(ADC4{slash}SDA)-Pad27)") (class "Default")
      (node (ref "U1") (pin "27") (pinfunction "PC4(ADC4/SDA)_27") (pintype "bidirectional"))
    )
    (net (code "100") (name "unconnected-(U1-PC5(ADC5{slash}SCL)-Pad28)") (class "Default")
      (node (ref "U1") (pin "28") (pinfunction "PC5(ADC5/SCL)_28") (pintype "bidirectional"))
    )
    (net (code "101") (name "unconnected-(U1-PD0(RXD)-Pad2)") (class "Default")
      (node (ref "U1") (pin "2") (pinfunction "PD0(RXD)_2") (pintype "bidirectional"))
    )
    (net (code "102") (name "unconnected-(U1-PD1(TXD)-Pad3)") (class "Default")
      (node (ref "U1") (pin "3") (pinfunction "PD1(TXD)_3") (pintype "bidirectional"))
    )
    (net (code "103") (name "unconnected-(U1-PD2(INT0)-Pad4)") (class "Default")
      (node (ref "U1") (pin "4") (pinfunction "PD2(INT0)_4") (pintype "bidirectional"))
    )
    (net (code "104") (name "unconnected-(U1-PD3(INT1)-Pad5)") (class "Default")
      (node (ref "U1") (pin "5") (pinfunction "PD3(INT1)_5") (pintype "bidirectional"))
    )
    (net (code "105") (name "unconnected-(U1-PD5(T1)-Pad11)") (class "Default")
      (node (ref "U1") (pin "11") (pinfunction "PD5(T1)_11") (pintype "bidirectional"))
    )
    (net (code "106") (name "unconnected-(U1-PD6(AIN0)-Pad12)") (class "Default")
      (node (ref "U1") (pin "12") (pinfunction "PD6(AIN0)_12") (pintype "bidirectional"))
    )
    (net (code "107") (name "unconnected-(U1-PD7(AIN1)-Pad13)") (class "Default")
      (node (ref "U1") (pin "13") (pinfunction "PD7(AIN1)_13") (pintype "bidirectional"))
    )
  )
)
